# 2s_AmplifierStage.net
KiCad netlist of a schematic drawn in EAGLE
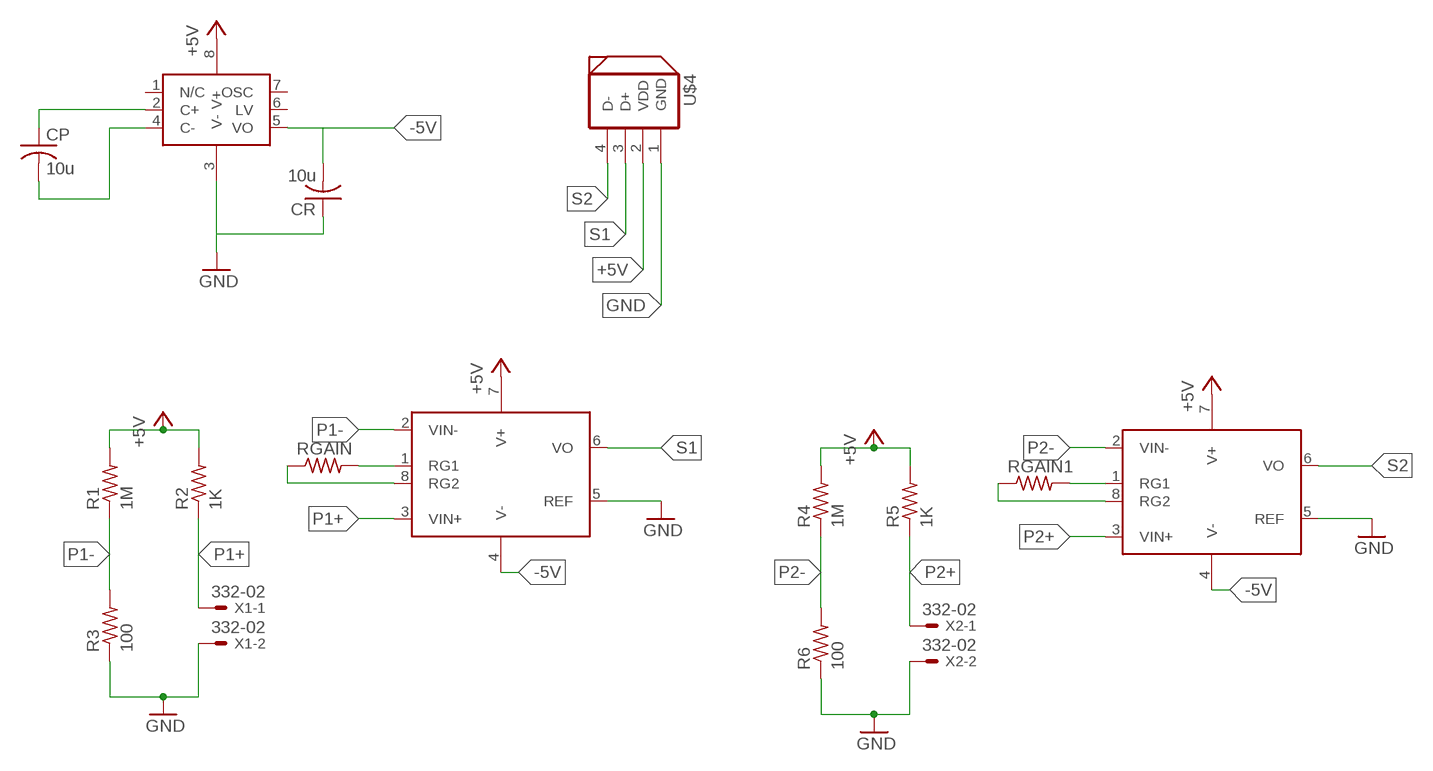
[diagram p0: schematic, sheet 1]

(export (version "E")
  (design (tool "Eeschema 10.0.6"))
  (components
    (comp (ref "CP")
      (value "10u")
      (footprint "eagle-import:C025-050X050")
      (libsource (lib "eagle-import") (part "C-US025-050X050"))
    )
    (comp (ref "CR")
      (value "10u")
      (footprint "eagle-import:C025-050X050")
      (libsource (lib "eagle-import") (part "C-US025-050X050"))
    )
    (comp (ref "R1")
      (value "1M")
      (footprint "eagle-import:0207_10")
      (libsource (lib "eagle-import") (part "R-US_0207/10"))
    )
    (comp (ref "R2")
      (value "1K")
      (footprint "eagle-import:0207_10")
      (libsource (lib "eagle-import") (part "R-US_0207/10"))
    )
    (comp (ref "R3")
      (value "100")
      (footprint "eagle-import:0207_10")
      (libsource (lib "eagle-import") (part "R-US_0207/10"))
    )
    (comp (ref "R4")
      (value "1M")
      (footprint "eagle-import:0207_10")
      (libsource (lib "eagle-import") (part "R-US_0207/10"))
    )
    (comp (ref "R5")
      (value "1K")
      (footprint "eagle-import:0207_10")
      (libsource (lib "eagle-import") (part "R-US_0207/10"))
    )
    (comp (ref "R6")
      (value "100")
      (footprint "eagle-import:0207_10")
      (libsource (lib "eagle-import") (part "R-US_0207/10"))
    )
    (comp (ref "RGAIN")
      (value "R-US_0207/10")
      (footprint "eagle-import:0207_10")
      (libsource (lib "eagle-import") (part "R-US_0207/10"))
    )
    (comp (ref "RGAIN1")
      (value "R-US_0207/10")
      (footprint "eagle-import:0207_10")
      (libsource (lib "eagle-import") (part "R-US_0207/10"))
    )
    (comp (ref "U$1")
      (value "LMC7660DI")
      (footprint "eagle-import:DIL08")
      (libsource (lib "eagle-import") (part "LMC7660DI"))
    )
    (comp (ref "U$2")
      (value "INA128PDIP8")
      (footprint "eagle-import:DIL08")
      (libsource (lib "eagle-import") (part "INA128PDIP8"))
    )
    (comp (ref "U$3")
      (value "INA128PDIP8")
      (footprint "eagle-import:DIL08")
      (libsource (lib "eagle-import") (part "INA128PDIP8"))
    )
    (comp (ref "U$4")
      (value "DYNAMIXEL_RS485")
      (footprint "eagle-import:DYNAMIXEL_SPOX_04")
      (libsource (lib "eagle-import") (part "DYNAMIXEL_RS485"))
    )
    (comp (ref "X1")
      (value "332-02")
      (footprint "eagle-import:332-02")
      (libsource (lib "eagle-import") (part "332-02"))
    )
    (comp (ref "X2")
      (value "332-02")
      (footprint "eagle-import:332-02")
      (libsource (lib "eagle-import") (part "332-02"))
    )
  )
  (nets
    (net (code "1") (name "+5V") (class "Default")
      (node (ref "R1") (pin "2") (pinfunction "2_2") (pintype "passive"))
      (node (ref "R2") (pin "2") (pinfunction "2_2") (pintype "passive"))
      (node (ref "R4") (pin "2") (pinfunction "2_2") (pintype "passive"))
      (node (ref "R5") (pin "2") (pinfunction "2_2") (pintype "passive"))
      (node (ref "U$1") (pin "8") (pinfunction "V+_8") (pintype "bidirectional"))
      (node (ref "U$2") (pin "7") (pinfunction "V+_7") (pintype "bidirectional"))
      (node (ref "U$3") (pin "7") (pinfunction "V+_7") (pintype "bidirectional"))
      (node (ref "U$4") (pin "2") (pinfunction "VDD_2") (pintype "power_in"))
    )
    (net (code "2") (name "-5V") (class "Default")
      (node (ref "CR") (pin "2") (pinfunction "2_2") (pintype "passive"))
      (node (ref "U$1") (pin "5") (pinfunction "VO_5") (pintype "bidirectional"))
      (node (ref "U$2") (pin "4") (pinfunction "V-_4") (pintype "bidirectional"))
      (node (ref "U$3") (pin "4") (pinfunction "V-_4") (pintype "bidirectional"))
    )
    (net (code "3") (name "GND") (class "Default")
      (node (ref "CR") (pin "1") (pinfunction "1_1") (pintype "passive"))
      (node (ref "R3") (pin "1") (pinfunction "1_1") (pintype "passive"))
      (node (ref "R6") (pin "1") (pinfunction "1_1") (pintype "passive"))
      (node (ref "U$1") (pin "3") (pinfunction "V-_3") (pintype "bidirectional"))
      (node (ref "U$2") (pin "5") (pinfunction "REF_5") (pintype "bidirectional"))
      (node (ref "U$3") (pin "5") (pinfunction "REF_5") (pintype "bidirectional"))
      (node (ref "U$4") (pin "1") (pinfunction "GND_1") (pintype "power_in"))
      (node (ref "X1") (pin "2") (pinfunction "S_2") (pintype "passive"))
      (node (ref "X2") (pin "2") (pinfunction "S_2") (pintype "passive"))
    )
    (net (code "4") (name "Net-(U$1-C+)") (class "Default")
      (node (ref "CP") (pin "1") (pinfunction "1_1") (pintype "passive"))
      (node (ref "U$1") (pin "2") (pinfunction "C+_2") (pintype "bidirectional"))
    )
    (net (code "5") (name "Net-(U$1-C-)") (class "Default")
      (node (ref "CP") (pin "2") (pinfunction "2_2") (pintype "passive"))
      (node (ref "U$1") (pin "4") (pinfunction "C-_4") (pintype "bidirectional"))
    )
    (net (code "6") (name "Net-(U$2-RG1)") (class "Default")
      (node (ref "RGAIN") (pin "2") (pinfunction "2_2") (pintype "passive"))
      (node (ref "U$2") (pin "1") (pinfunction "RG1_1") (pintype "bidirectional"))
    )
    (net (code "7") (name "Net-(U$2-RG2)") (class "Default")
      (node (ref "RGAIN") (pin "1") (pinfunction "1_1") (pintype "passive"))
      (node (ref "U$2") (pin "8") (pinfunction "RG2_8") (pintype "bidirectional"))
    )
    (net (code "8") (name "Net-(U$3-RG1)") (class "Default")
      (node (ref "RGAIN1") (pin "2") (pinfunction "2_2") (pintype "passive"))
      (node (ref "U$3") (pin "1") (pinfunction "RG1_1") (pintype "bidirectional"))
    )
    (net (code "9") (name "Net-(U$3-RG2)") (class "Default")
      (node (ref "RGAIN1") (pin "1") (pinfunction "1_1") (pintype "passive"))
      (node (ref "U$3") (pin "8") (pinfunction "RG2_8") (pintype "bidirectional"))
    )
    (net (code "10") (name "P1+") (class "Default")
      (node (ref "R2") (pin "1") (pinfunction "1_1") (pintype "passive"))
      (node (ref "U$2") (pin "3") (pinfunction "VIN+_3") (pintype "bidirectional"))
      (node (ref "X1") (pin "1") (pinfunction "S_1") (pintype "passive"))
    )
    (net (code "11") (name "P1-") (class "Default")
      (node (ref "R1") (pin "1") (pinfunction "1_1") (pintype "passive"))
      (node (ref "R3") (pin "2") (pinfunction "2_2") (pintype "passive"))
      (node (ref "U$2") (pin "2") (pinfunction "VIN-_2") (pintype "bidirectional"))
    )
    (net (code "12") (name "P2+") (class "Default")
      (node (ref "R5") (pin "1") (pinfunction "1_1") (pintype "passive"))
      (node (ref "U$3") (pin "3") (pinfunction "VIN+_3") (pintype "bidirectional"))
      (node (ref "X2") (pin "1") (pinfunction "S_1") (pintype "passive"))
    )
    (net (code "13") (name "P2-") (class "Default")
      (node (ref "R4") (pin "1") (pinfunction "1_1") (pintype "passive"))
      (node (ref "R6") (pin "2") (pinfunction "2_2") (pintype "passive"))
      (node (ref "U$3") (pin "2") (pinfunction "VIN-_2") (pintype "bidirectional"))
    )
    (net (code "14") (name "S1") (class "Default")
      (node (ref "U$2") (pin "6") (pinfunction "VO_6") (pintype "output"))
      (node (ref "U$4") (pin "3") (pinfunction "D+_3") (pintype "bidirectional"))
    )
    (net (code "15") (name "S2") (class "Default")
      (node (ref "U$3") (pin "6") (pinfunction "VO_6") (pintype "output"))
      (node (ref "U$4") (pin "4") (pinfunction "D-_4") (pintype "bidirectional"))
    )
    (net (code "16") (name "unconnected-(U$1-LV-Pad6)") (class "Default")
      (node (ref "U$1") (pin "6") (pinfunction "LV_6") (pintype "bidirectional"))
    )
    (net (code "17") (name "unconnected-(U$1-N{slash}C-Pad1)") (class "Default")
      (node (ref "U$1") (pin "1") (pinfunction "N/C_1") (pintype "bidirectional"))
    )
    (net (code "18") (name "unconnected-(U$1-OSC-Pad7)") (class "Default")
      (node (ref "U$1") (pin "7") (pinfunction "OSC_7") (pintype "bidirectional"))
    )
  )
)
